# RaspberryPiSocket.net
KiCad netlist of a schematic drawn in EAGLE
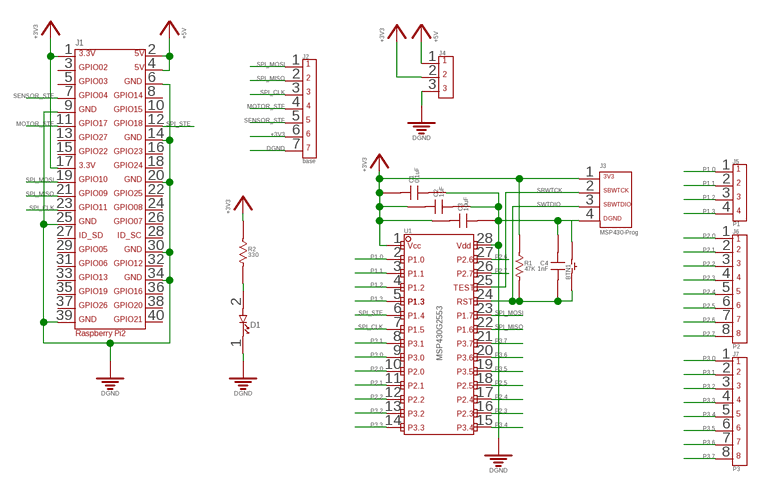
[diagram p0: schematic, sheet 1]

(export (version "E")
  (design (tool "Eeschema 10.0.6"))
  (components
    (comp (ref "BTN1")
      (value "BTN_NORMAL_OFF_6_3.5_SMD")
      (footprint "eagle-import:BTN_6_3.5_SMD")
      (libsource (lib "eagle-import") (part "BTN_NORMAL_OFF_6_3.5_SMD"))
    )
    (comp (ref "C1")
      (value "0.1uF")
      (footprint "eagle-import:0805")
      (libsource (lib "eagle-import") (part "CAPACITOR_FIXED_0805"))
    )
    (comp (ref "C2")
      (value "1uF")
      (footprint "eagle-import:0805")
      (libsource (lib "eagle-import") (part "CAPACITOR_FIXED_0805"))
    )
    (comp (ref "C3")
      (value "10uF")
      (footprint "eagle-import:0805")
      (libsource (lib "eagle-import") (part "CAPACITOR_FIXED_0805"))
    )
    (comp (ref "C4")
      (value "1nF")
      (footprint "eagle-import:0805")
      (libsource (lib "eagle-import") (part "CAPACITOR_FIXED_0805"))
    )
    (comp (ref "D1")
      (value "LED_0805")
      (footprint "eagle-import:0805DIODE")
      (libsource (lib "eagle-import") (part "LED_0805"))
    )
    (comp (ref "J1")
      (value "RPI2")
      (footprint "eagle-import:RPI2")
      (libsource (lib "eagle-import") (part "RPI2"))
    )
    (comp (ref "J2")
      (value "base")
      (footprint "eagle-import:7PIN_HEADER_VERT_PITCH2.54MM_TH")
      (libsource (lib "eagle-import") (part "7PIN_HEADER_VERT_PITCH2.54MM_TH"))
    )
    (comp (ref "J3")
      (value "MSP430-PROG_NORMAL")
      (footprint "eagle-import:4PIN_HEADER_PITCH2.54MM_TH")
      (libsource (lib "eagle-import") (part "MSP430-PROG_NORMAL"))
    )
    (comp (ref "J4")
      (value "3PIN_HEADER_PITCH2.54MM_TH")
      (footprint "eagle-import:3PIN_HEADER_PITCH2.54MM_TH")
      (libsource (lib "eagle-import") (part "3PIN_HEADER_PITCH2.54MM_TH"))
    )
    (comp (ref "J5")
      (value "P1")
      (footprint "eagle-import:4PIN_HEADER_PITCH2.54MM_TH")
      (libsource (lib "eagle-import") (part "4PIN_HEADER_PITCH2.54MM_TH"))
    )
    (comp (ref "J6")
      (value "P2")
      (footprint "eagle-import:8PIN_HEADER_PITCH2.54MM_TH")
      (libsource (lib "eagle-import") (part "8PIN_HEADER_PITCH2.54MM_TH"))
    )
    (comp (ref "J7")
      (value "P3")
      (footprint "eagle-import:8PIN_HEADER_PITCH2.54MM_TH")
      (libsource (lib "eagle-import") (part "8PIN_HEADER_PITCH2.54MM_TH"))
    )
    (comp (ref "R1")
      (value "47K")
      (footprint "eagle-import:0805")
      (libsource (lib "eagle-import") (part "RESISTOR_0805"))
    )
    (comp (ref "R2")
      (value "330")
      (footprint "eagle-import:0805")
      (libsource (lib "eagle-import") (part "RESISTOR_0805"))
    )
    (comp (ref "U1")
      (value "MSP430G2553_24IO_28PIN_TSSOP")
      (footprint "eagle-import:TSSOP-28")
      (libsource (lib "eagle-import") (part "MSP430G2553_24IO_28PIN_TSSOP"))
    )
  )
  (nets
    (net (code "1") (name "+3V3") (class "Default")
      (node (ref "C1") (pin "1") (pinfunction "1_1") (pintype "passive"))
      (node (ref "C2") (pin "1") (pinfunction "1_1") (pintype "passive"))
      (node (ref "C3") (pin "1") (pinfunction "1_1") (pintype "passive"))
      (node (ref "J1") (pin "1") (pinfunction "1_1") (pintype "passive"))
      (node (ref "J1") (pin "17") (pinfunction "17_17") (pintype "passive"))
      (node (ref "J2") (pin "6") (pinfunction "6_6") (pintype "passive"))
      (node (ref "J3") (pin "1") (pinfunction "1_1") (pintype "passive"))
      (node (ref "J4") (pin "2") (pinfunction "2_2") (pintype "passive"))
      (node (ref "R1") (pin "1") (pinfunction "1_1") (pintype "passive"))
      (node (ref "R2") (pin "1") (pinfunction "1_1") (pintype "passive"))
      (node (ref "U1") (pin "1") (pinfunction "1_1") (pintype "passive"))
    )
    (net (code "2") (name "+5V") (class "Default")
      (node (ref "J1") (pin "2") (pinfunction "2_2") (pintype "passive"))
      (node (ref "J1") (pin "4") (pinfunction "4_4") (pintype "passive"))
      (node (ref "J4") (pin "1") (pinfunction "1_1") (pintype "passive"))
    )
    (net (code "3") (name "/MOTOR_STE") (class "Default")
      (node (ref "J1") (pin "11") (pinfunction "11_11") (pintype "passive"))
      (node (ref "J2") (pin "4") (pinfunction "4_4") (pintype "passive"))
    )
    (net (code "4") (name "/P1.0") (class "Default")
      (node (ref "J5") (pin "1") (pinfunction "1_1") (pintype "passive"))
      (node (ref "U1") (pin "2") (pinfunction "2_2") (pintype "passive"))
    )
    (net (code "5") (name "/P1.1") (class "Default")
      (node (ref "J5") (pin "2") (pinfunction "2_2") (pintype "passive"))
      (node (ref "U1") (pin "3") (pinfunction "3_3") (pintype "passive"))
    )
    (net (code "6") (name "/P1.2") (class "Default")
      (node (ref "J5") (pin "3") (pinfunction "3_3") (pintype "passive"))
      (node (ref "U1") (pin "4") (pinfunction "4_4") (pintype "passive"))
    )
    (net (code "7") (name "/P1.3") (class "Default")
      (node (ref "J5") (pin "4") (pinfunction "4_4") (pintype "passive"))
      (node (ref "U1") (pin "5") (pinfunction "5_5") (pintype "passive"))
    )
    (net (code "8") (name "/P2.0") (class "Default")
      (node (ref "J6") (pin "1") (pinfunction "1_1") (pintype "passive"))
      (node (ref "U1") (pin "10") (pinfunction "10_10") (pintype "passive"))
    )
    (net (code "9") (name "/P2.1") (class "Default")
      (node (ref "J6") (pin "2") (pinfunction "2_2") (pintype "passive"))
      (node (ref "U1") (pin "11") (pinfunction "11_11") (pintype "passive"))
    )
    (net (code "10") (name "/P2.2") (class "Default")
      (node (ref "J6") (pin "3") (pinfunction "3_3") (pintype "passive"))
      (node (ref "U1") (pin "12") (pinfunction "12_12") (pintype "passive"))
    )
    (net (code "11") (name "/P2.3") (class "Default")
      (node (ref "J6") (pin "4") (pinfunction "4_4") (pintype "passive"))
      (node (ref "U1") (pin "16") (pinfunction "16_16") (pintype "passive"))
    )
    (net (code "12") (name "/P2.4") (class "Default")
      (node (ref "J6") (pin "5") (pinfunction "5_5") (pintype "passive"))
      (node (ref "U1") (pin "17") (pinfunction "17_17") (pintype "passive"))
    )
    (net (code "13") (name "/P2.5") (class "Default")
      (node (ref "J6") (pin "6") (pinfunction "6_6") (pintype "passive"))
      (node (ref "U1") (pin "18") (pinfunction "18_18") (pintype "passive"))
    )
    (net (code "14") (name "/P2.6") (class "Default")
      (node (ref "J6") (pin "7") (pinfunction "7_7") (pintype "passive"))
      (node (ref "U1") (pin "27") (pinfunction "27_27") (pintype "passive"))
    )
    (net (code "15") (name "/P2.7") (class "Default")
      (node (ref "J6") (pin "8") (pinfunction "8_8") (pintype "passive"))
      (node (ref "U1") (pin "26") (pinfunction "26_26") (pintype "passive"))
    )
    (net (code "16") (name "/P3.0") (class "Default")
      (node (ref "J7") (pin "1") (pinfunction "1_1") (pintype "passive"))
      (node (ref "U1") (pin "9") (pinfunction "9_9") (pintype "passive"))
    )
    (net (code "17") (name "/P3.1") (class "Default")
      (node (ref "J7") (pin "2") (pinfunction "2_2") (pintype "passive"))
      (node (ref "U1") (pin "8") (pinfunction "8_8") (pintype "passive"))
    )
    (net (code "18") (name "/P3.2") (class "Default")
      (node (ref "J7") (pin "3") (pinfunction "3_3") (pintype "passive"))
      (node (ref "U1") (pin "13") (pinfunction "13_13") (pintype "passive"))
    )
    (net (code "19") (name "/P3.3") (class "Default")
      (node (ref "J7") (pin "4") (pinfunction "4_4") (pintype "passive"))
      (node (ref "U1") (pin "14") (pinfunction "14_14") (pintype "passive"))
    )
    (net (code "20") (name "/P3.4") (class "Default")
      (node (ref "J7") (pin "5") (pinfunction "5_5") (pintype "passive"))
      (node (ref "U1") (pin "15") (pinfunction "15_15") (pintype "passive"))
    )
    (net (code "21") (name "/P3.5") (class "Default")
      (node (ref "J7") (pin "6") (pinfunction "6_6") (pintype "passive"))
      (node (ref "U1") (pin "19") (pinfunction "19_19") (pintype "passive"))
    )
    (net (code "22") (name "/P3.6") (class "Default")
      (node (ref "J7") (pin "7") (pinfunction "7_7") (pintype "passive"))
      (node (ref "U1") (pin "20") (pinfunction "20_20") (pintype "passive"))
    )
    (net (code "23") (name "/P3.7") (class "Default")
      (node (ref "J7") (pin "8") (pinfunction "8_8") (pintype "passive"))
      (node (ref "U1") (pin "21") (pinfunction "21_21") (pintype "passive"))
    )
    (net (code "24") (name "/SBWTCK") (class "Default")
      (node (ref "J3") (pin "2") (pinfunction "2_2") (pintype "passive"))
      (node (ref "U1") (pin "25") (pinfunction "25_25") (pintype "passive"))
    )
    (net (code "25") (name "/SENSOR_STE") (class "Default")
      (node (ref "J1") (pin "7") (pinfunction "7_7") (pintype "passive"))
      (node (ref "J2") (pin "5") (pinfunction "5_5") (pintype "passive"))
    )
    (net (code "26") (name "/SPI_CLK") (class "Default")
      (node (ref "J1") (pin "23") (pinfunction "23_23") (pintype "passive"))
      (node (ref "J2") (pin "3") (pinfunction "3_3") (pintype "passive"))
      (node (ref "U1") (pin "7") (pinfunction "7_7") (pintype "passive"))
    )
    (net (code "27") (name "/SPI_MISO") (class "Default")
      (node (ref "J1") (pin "21") (pinfunction "21_21") (pintype "passive"))
      (node (ref "J2") (pin "2") (pinfunction "2_2") (pintype "passive"))
      (node (ref "U1") (pin "22") (pinfunction "22_22") (pintype "passive"))
    )
    (net (code "28") (name "/SPI_MOSI") (class "Default")
      (node (ref "J1") (pin "19") (pinfunction "19_19") (pintype "passive"))
      (node (ref "J2") (pin "1") (pinfunction "1_1") (pintype "passive"))
      (node (ref "U1") (pin "23") (pinfunction "23_23") (pintype "passive"))
    )
    (net (code "29") (name "/SPI_STE") (class "Default")
      (node (ref "J1") (pin "12") (pinfunction "12_12") (pintype "passive"))
      (node (ref "U1") (pin "6") (pinfunction "6_6") (pintype "passive"))
    )
    (net (code "30") (name "/SWTDIO") (class "Default")
      (node (ref "BTN1") (pin "1") (pinfunction "1_1") (pintype "passive"))
      (node (ref "C4") (pin "2") (pinfunction "2_2") (pintype "passive"))
      (node (ref "J3") (pin "3") (pinfunction "3_3") (pintype "passive"))
      (node (ref "R1") (pin "2") (pinfunction "2_2") (pintype "passive"))
      (node (ref "U1") (pin "24") (pinfunction "24_24") (pintype "passive"))
    )
    (net (code "31") (name "DGND") (class "Default")
      (node (ref "BTN1") (pin "2") (pinfunction "2_2") (pintype "passive"))
      (node (ref "C1") (pin "2") (pinfunction "2_2") (pintype "passive"))
      (node (ref "C2") (pin "2") (pinfunction "2_2") (pintype "passive"))
      (node (ref "C3") (pin "2") (pinfunction "2_2") (pintype "passive"))
      (node (ref "C4") (pin "1") (pinfunction "1_1") (pintype "passive"))
      (node (ref "D1") (pin "1") (pinfunction "1_1") (pintype "passive"))
      (node (ref "J1") (pin "14") (pinfunction "14_14") (pintype "passive"))
      (node (ref "J1") (pin "20") (pinfunction "20_20") (pintype "passive"))
      (node (ref "J1") (pin "25") (pinfunction "25_25") (pintype "passive"))
      (node (ref "J1") (pin "30") (pinfunction "30_30") (pintype "passive"))
      (node (ref "J1") (pin "34") (pinfunction "34_34") (pintype "passive"))
      (node (ref "J1") (pin "39") (pinfunction "39_39") (pintype "passive"))
      (node (ref "J1") (pin "6") (pinfunction "6_6") (pintype "passive"))
      (node (ref "J1") (pin "9") (pinfunction "9_9") (pintype "passive"))
      (node (ref "J2") (pin "7") (pinfunction "7_7") (pintype "passive"))
      (node (ref "J3") (pin "4") (pinfunction "4_4") (pintype "passive"))
      (node (ref "J4") (pin "3") (pinfunction "3_3") (pintype "passive"))
      (node (ref "U1") (pin "28") (pinfunction "P$7_28") (pintype "passive"))
    )
    (net (code "32") (name "Net-(D1-Pad2)") (class "Default")
      (node (ref "D1") (pin "2") (pinfunction "2_2") (pintype "passive"))
      (node (ref "R2") (pin "2") (pinfunction "2_2") (pintype "passive"))
    )
    (net (code "33") (name "unconnected-(J1-Pad3)") (class "Default")
      (node (ref "J1") (pin "3") (pinfunction "3_3") (pintype "passive"))
    )
    (net (code "34") (name "unconnected-(J1-Pad5)") (class "Default")
      (node (ref "J1") (pin "5") (pinfunction "5_5") (pintype "passive"))
    )
    (net (code "35") (name "unconnected-(J1-Pad8)") (class "Default")
      (node (ref "J1") (pin "8") (pinfunction "8_8") (pintype "passive"))
    )
    (net (code "36") (name "unconnected-(J1-Pad10)") (class "Default")
      (node (ref "J1") (pin "10") (pinfunction "10_10") (pintype "passive"))
    )
    (net (code "37") (name "unconnected-(J1-Pad13)") (class "Default")
      (node (ref "J1") (pin "13") (pinfunction "13_13") (pintype "passive"))
    )
    (net (code "38") (name "unconnected-(J1-Pad15)") (class "Default")
      (node (ref "J1") (pin "15") (pinfunction "15_15") (pintype "passive"))
    )
    (net (code "39") (name "unconnected-(J1-Pad16)") (class "Default")
      (node (ref "J1") (pin "16") (pinfunction "16_16") (pintype "passive"))
    )
    (net (code "40") (name "unconnected-(J1-Pad18)") (class "Default")
      (node (ref "J1") (pin "18") (pinfunction "18_18") (pintype "passive"))
    )
    (net (code "41") (name "unconnected-(J1-Pad22)") (class "Default")
      (node (ref "J1") (pin "22") (pinfunction "22_22") (pintype "passive"))
    )
    (net (code "42") (name "unconnected-(J1-Pad24)") (class "Default")
      (node (ref "J1") (pin "24") (pinfunction "24_24") (pintype "passive"))
    )
    (net (code "43") (name "unconnected-(J1-Pad26)") (class "Default")
      (node (ref "J1") (pin "26") (pinfunction "26_26") (pintype "passive"))
    )
    (net (code "44") (name "unconnected-(J1-Pad27)") (class "Default")
      (node (ref "J1") (pin "27") (pinfunction "27_27") (pintype "passive"))
    )
    (net (code "45") (name "unconnected-(J1-Pad28)") (class "Default")
      (node (ref "J1") (pin "28") (pinfunction "28_28") (pintype "passive"))
    )
    (net (code "46") (name "unconnected-(J1-Pad29)") (class "Default")
      (node (ref "J1") (pin "29") (pinfunction "29_29") (pintype "passive"))
    )
    (net (code "47") (name "unconnected-(J1-Pad31)") (class "Default")
      (node (ref "J1") (pin "31") (pinfunction "31_31") (pintype "passive"))
    )
    (net (code "48") (name "unconnected-(J1-Pad32)") (class "Default")
      (node (ref "J1") (pin "32") (pinfunction "32_32") (pintype "passive"))
    )
    (net (code "49") (name "unconnected-(J1-Pad33)") (class "Default")
      (node (ref "J1") (pin "33") (pinfunction "33_33") (pintype "passive"))
    )
    (net (code "50") (name "unconnected-(J1-Pad35)") (class "Default")
      (node (ref "J1") (pin "35") (pinfunction "35_35") (pintype "passive"))
    )
    (net (code "51") (name "unconnected-(J1-Pad36)") (class "Default")
      (node (ref "J1") (pin "36") (pinfunction "36_36") (pintype "passive"))
    )
    (net (code "52") (name "unconnected-(J1-Pad37)") (class "Default")
      (node (ref "J1") (pin "37") (pinfunction "37_37") (pintype "passive"))
    )
    (net (code "53") (name "unconnected-(J1-Pad38)") (class "Default")
      (node (ref "J1") (pin "38") (pinfunction "38_38") (pintype "passive"))
    )
    (net (code "54") (name "unconnected-(J1-Pad40)") (class "Default")
      (node (ref "J1") (pin "40") (pinfunction "40_40") (pintype "passive"))
    )
  )
)
